# pc_sensything_v1_3.net
KiCad netlist of a schematic drawn in EAGLE
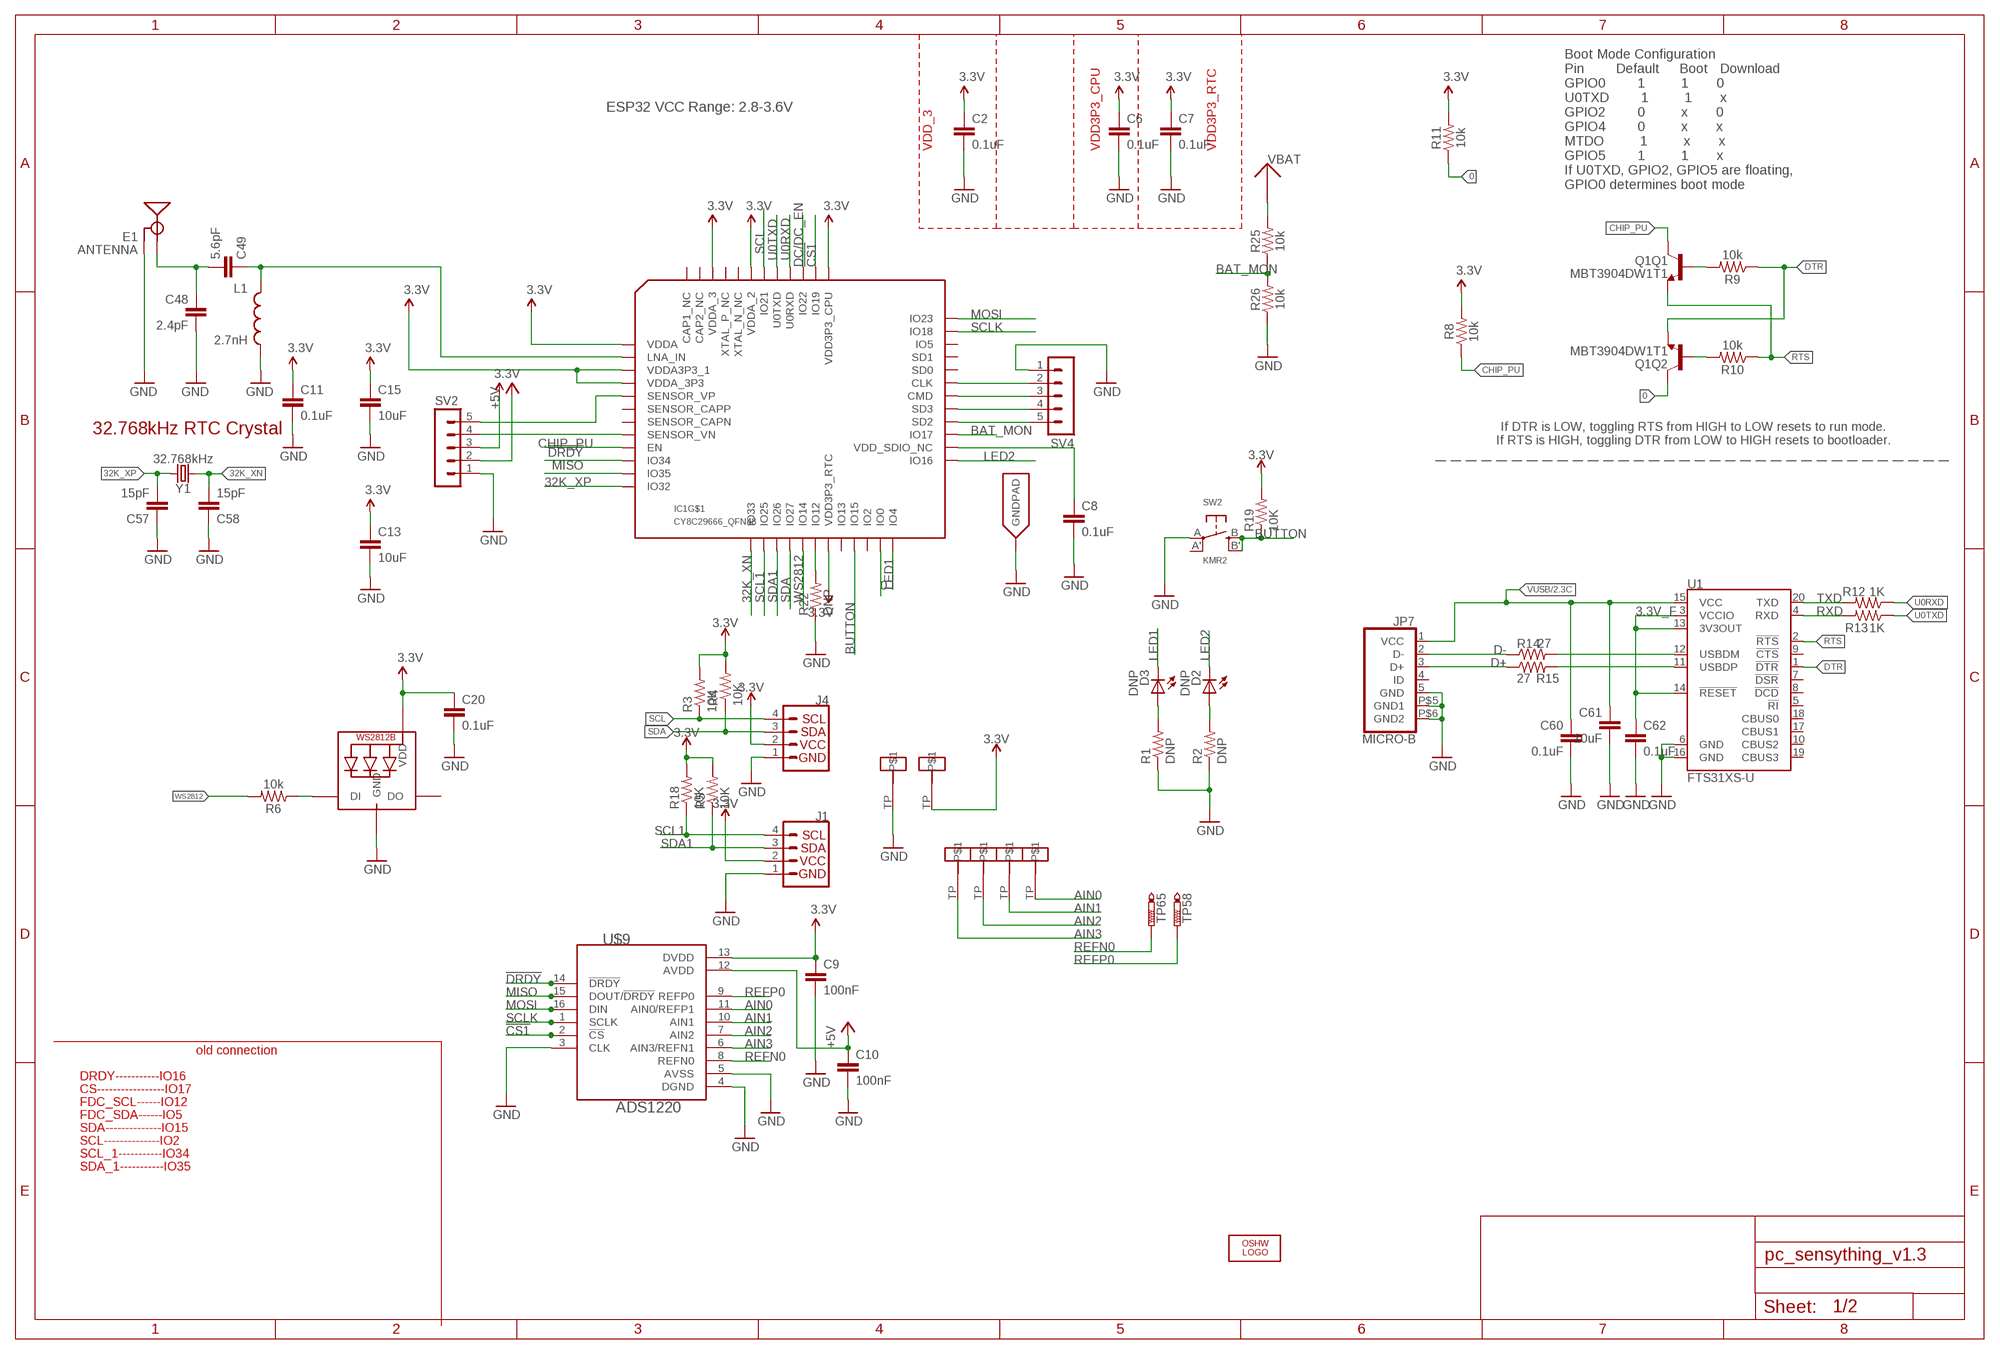
[diagram p0: schematic, sheet 1]
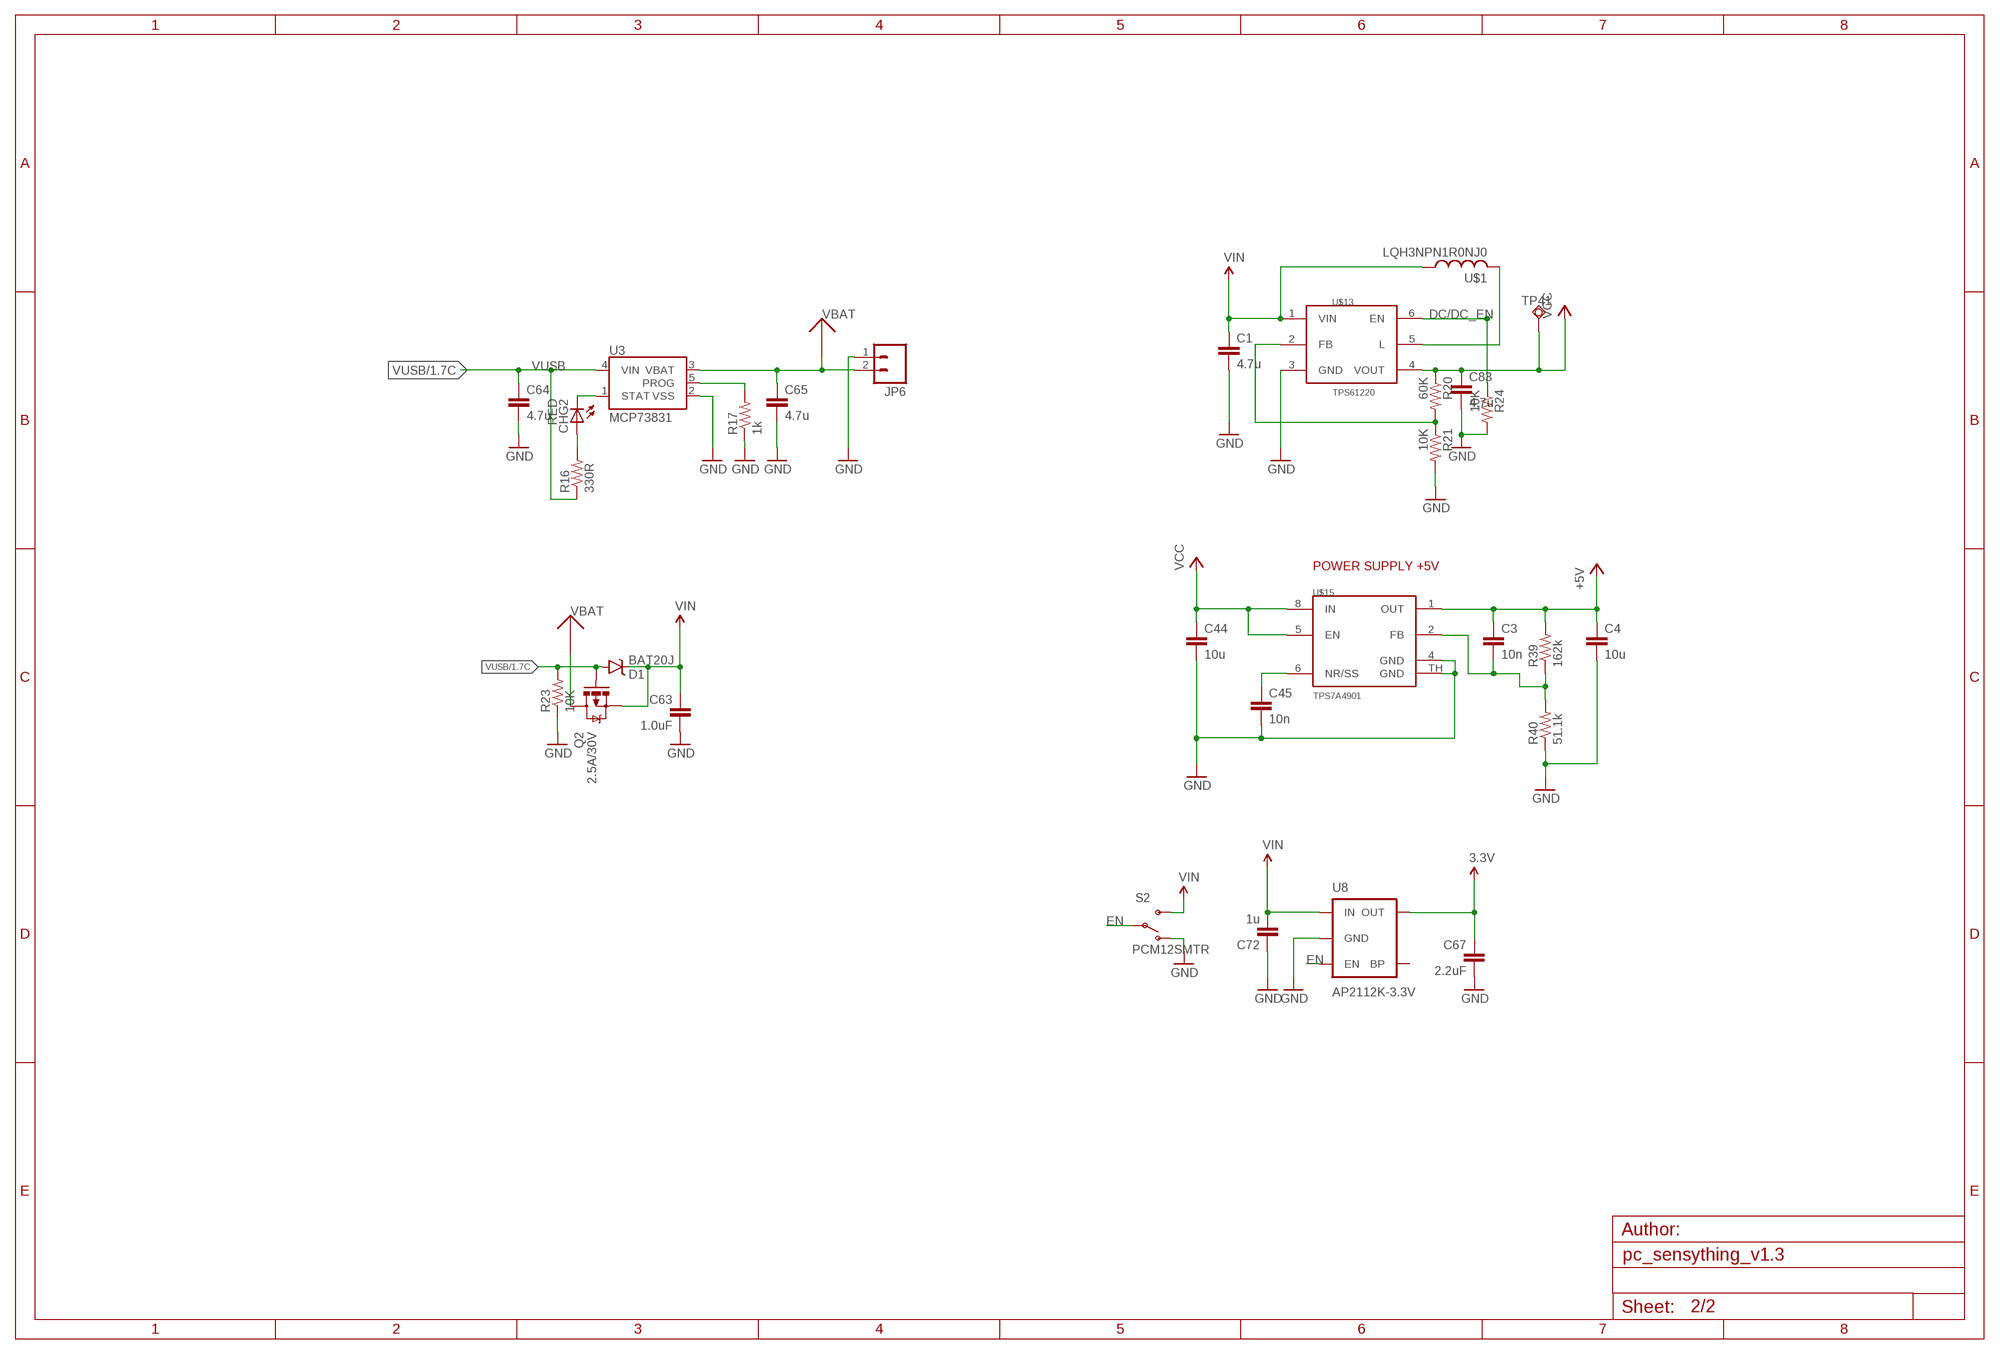
[diagram p1: schematic, sheet 2]

(export (version "E")
  (design (tool "Eeschema 10.0.6"))
  (components
    (comp (ref "C2")
      (value "0.1uF")
      (footprint "eagle-import:0402")
      (libsource (lib "eagle-import") (part "0.1UF-0402-16V-10%"))
    )
    (comp (ref "C6")
      (value "0.1uF")
      (footprint "eagle-import:0402")
      (libsource (lib "eagle-import") (part "0.1UF-0402-16V-10%"))
    )
    (comp (ref "C7")
      (value "0.1uF")
      (footprint "eagle-import:0402")
      (libsource (lib "eagle-import") (part "0.1UF-0402-16V-10%"))
    )
    (comp (ref "C8")
      (value "0.1uF")
      (footprint "eagle-import:0402")
      (libsource (lib "eagle-import") (part "0.1UF-0402-16V-10%"))
    )
    (comp (ref "C9")
      (value "100nF")
      (footprint "eagle-import:C0805")
      (libsource (lib "eagle-import") (part "C-EUC0805"))
    )
    (comp (ref "C10")
      (value "100nF")
      (footprint "eagle-import:C0805")
      (libsource (lib "eagle-import") (part "C-EUC0805"))
    )
    (comp (ref "C11")
      (value "0.1uF")
      (footprint "eagle-import:0402")
      (libsource (lib "eagle-import") (part "0.1UF-0402-16V-10%"))
    )
    (comp (ref "C13")
      (value "10uF")
      (footprint "eagle-import:0603")
      (libsource (lib "eagle-import") (part "10UF-0603-6.3V-20%"))
    )
    (comp (ref "C15")
      (value "10uF")
      (footprint "eagle-import:0603")
      (libsource (lib "eagle-import") (part "10UF-0603-6.3V-20%"))
    )
    (comp (ref "C20")
      (value "0.1uF")
      (footprint "eagle-import:0603")
      (libsource (lib "eagle-import") (part "0.1UF-0603-25V-(+80/-20%)"))
    )
    (comp (ref "C48")
      (value "2.4pF")
      (footprint "eagle-import:0603")
      (libsource (lib "eagle-import") (part "2.4PF-0603-50V-5%"))
    )
    (comp (ref "C49")
      (value "5.6pF")
      (footprint "eagle-import:0603")
      (libsource (lib "eagle-import") (part "5.6PF-50V-5%(0603)"))
    )
    (comp (ref "C57")
      (value "15pF")
      (footprint "eagle-import:0603")
      (libsource (lib "eagle-import") (part "15PF-0603-50V-5%"))
    )
    (comp (ref "C58")
      (value "15pF")
      (footprint "eagle-import:0603")
      (libsource (lib "eagle-import") (part "15PF-0603-50V-5%"))
    )
    (comp (ref "C60")
      (value "0.1uF")
      (footprint "eagle-import:C0402")
      (libsource (lib "eagle-import") (part "C-EUC0402"))
    )
    (comp (ref "C61")
      (value "10uF")
      (footprint "eagle-import:C0805")
      (libsource (lib "eagle-import") (part "C-EUC0805"))
    )
    (comp (ref "C62")
      (value "0.1uF")
      (footprint "eagle-import:C0402")
      (libsource (lib "eagle-import") (part "C-EUC0402"))
    )
    (comp (ref "D2")
      (value "DNP")
      (footprint "eagle-import:CHIPLED_0603")
      (libsource (lib "eagle-import") (part "LEDCHIPLED_0603"))
    )
    (comp (ref "D3")
      (value "DNP")
      (footprint "eagle-import:CHIPLED_0603")
      (libsource (lib "eagle-import") (part "LEDCHIPLED_0603"))
    )
    (comp (ref "E1")
      (value "ANTENNA")
      (footprint "eagle-import:TRACE_ANTENNA_2.4GHZ_25.7MM_TUNED")
      (libsource (lib "eagle-import") (part "ANTENNATRACE-TUNED"))
    )
    (comp (ref "IC1")
      (value "CY8C29666_QFN48")
      (footprint "eagle-import:QFN48")
      (libsource (lib "eagle-import") (part "CY8C29666_QFN48"))
    )
    (comp (ref "J1")
      (value "QWIIC_CONNECTORJS-1MM")
      (footprint "eagle-import:1X04_1MM_RA")
      (libsource (lib "eagle-import") (part "QWIIC_CONNECTORJS-1MM"))
    )
    (comp (ref "J4")
      (value "QWIIC_CONNECTORJS-1MM")
      (footprint "eagle-import:1X04_1MM_RA")
      (libsource (lib "eagle-import") (part "QWIIC_CONNECTORJS-1MM"))
    )
    (comp (ref "JP7")
      (value "MICRO-B")
      (footprint "eagle-import:MICRO-B")
      (libsource (lib "eagle-import") (part "MICRO-B"))
    )
    (comp (ref "L1")
      (value "2.7nH")
      (footprint "eagle-import:0603")
      (libsource (lib "eagle-import") (part "INDUCTOR0603"))
    )
    (comp (ref "LED1")
      (value "WS2812B5050")
      (footprint "eagle-import:WS2812B")
      (libsource (lib "eagle-import") (part "WS2812B5050"))
    )
    (comp (ref "LOGO3")
      (value "OSHW_LOGO_FILLX0200-NT")
      (footprint "eagle-import:OSHW_FILLX200_NOTEXT")
      (libsource (lib "eagle-import") (part "OSHW_LOGO_FILLX0200-NT"))
    )
    (comp (ref "Q1")
      (value "MBT3904DW1T1")
      (footprint "eagle-import:SC70-6")
      (libsource (lib "eagle-import") (part "MBT3904DW1T1"))
    )
    (comp (ref "R1")
      (value "DNP")
      (footprint "eagle-import:R0402")
      (libsource (lib "eagle-import") (part "R-US_R0402"))
    )
    (comp (ref "R2")
      (value "DNP")
      (footprint "eagle-import:R0402")
      (libsource (lib "eagle-import") (part "R-US_R0402"))
    )
    (comp (ref "R3")
      (value "10K")
      (footprint "eagle-import:R0402")
      (libsource (lib "eagle-import") (part "R-US_R0402"))
    )
    (comp (ref "R4")
      (value "10K")
      (footprint "eagle-import:R0402")
      (libsource (lib "eagle-import") (part "R-US_R0402"))
    )
    (comp (ref "R5")
      (value "10K")
      (footprint "eagle-import:R0402")
      (libsource (lib "eagle-import") (part "R-US_R0402"))
    )
    (comp (ref "R6")
      (value "10k")
      (footprint "eagle-import:0603")
      (libsource (lib "eagle-import") (part "10KOHM-1/10W-1%(0603)0603"))
    )
    (comp (ref "R8")
      (value "10k")
      (footprint "eagle-import:0603")
      (libsource (lib "eagle-import") (part "10KOHM-1/10W-1%(0603)0603"))
    )
    (comp (ref "R9")
      (value "10k")
      (footprint "eagle-import:0603")
      (libsource (lib "eagle-import") (part "10KOHM-0603-1/10W-1%"))
    )
    (comp (ref "R10")
      (value "10k")
      (footprint "eagle-import:0603")
      (libsource (lib "eagle-import") (part "10KOHM-0603-1/10W-1%"))
    )
    (comp (ref "R11")
      (value "10k")
      (footprint "eagle-import:0603")
      (libsource (lib "eagle-import") (part "10KOHM-1/10W-1%(0603)0603"))
    )
    (comp (ref "R12")
      (value "1K")
      (footprint "eagle-import:R0402")
      (libsource (lib "eagle-import") (part "R-US_R0402"))
    )
    (comp (ref "R13")
      (value "1K")
      (footprint "eagle-import:R0402")
      (libsource (lib "eagle-import") (part "R-US_R0402"))
    )
    (comp (ref "R14")
      (value "27")
      (footprint "eagle-import:R0402")
      (libsource (lib "eagle-import") (part "R-US_R0402"))
    )
    (comp (ref "R15")
      (value "27")
      (footprint "eagle-import:R0402")
      (libsource (lib "eagle-import") (part "R-US_R0402"))
    )
    (comp (ref "R18")
      (value "10K")
      (footprint "eagle-import:R0402")
      (libsource (lib "eagle-import") (part "R-US_R0402"))
    )
    (comp (ref "R19")
      (value "10K")
      (footprint "eagle-import:R0402")
      (libsource (lib "eagle-import") (part "R-US_R0402"))
    )
    (comp (ref "R22")
      (value "DNP")
      (footprint "eagle-import:R0402")
      (libsource (lib "eagle-import") (part "R-US_R0402"))
    )
    (comp (ref "R25")
      (value "10k")
      (footprint "eagle-import:0603")
      (libsource (lib "eagle-import") (part "10KOHM-1/10W-1%(0603)0603"))
    )
    (comp (ref "R26")
      (value "10k")
      (footprint "eagle-import:0603")
      (libsource (lib "eagle-import") (part "10KOHM-1/10W-1%(0603)0603"))
    )
    (comp (ref "SV2")
      (value "MA05-1")
      (footprint "eagle-import:MA05-1")
      (libsource (lib "eagle-import") (part "MA05-1"))
    )
    (comp (ref "SV4")
      (value "MA05-1")
      (footprint "eagle-import:MA05-1")
      (libsource (lib "eagle-import") (part "MA05-1"))
    )
    (comp (ref "SW2")
      (value "KMR2")
      (footprint "eagle-import:BTN_KMR2_4.6X2.8")
      (libsource (lib "eagle-import") (part "SWITCH_TACT_SMT4.6X2.8"))
    )
    (comp (ref "TP58")
      (value "PTR1PAD1-13")
      (footprint "eagle-import:P1-13")
      (libsource (lib "eagle-import") (part "PTR1PAD1-13"))
    )
    (comp (ref "TP65")
      (value "PTR1PAD1-13")
      (footprint "eagle-import:P1-13")
      (libsource (lib "eagle-import") (part "PTR1PAD1-13"))
    )
    (comp (ref "U$3")
      (value "SENSYTHING_CON")
      (footprint "eagle-import:SENSYTHING_CON")
      (libsource (lib "eagle-import") (part "SENSYTHING_CON"))
    )
    (comp (ref "U$7")
      (value "SENSYTHING_CON")
      (footprint "eagle-import:SENSYTHING_CON")
      (libsource (lib "eagle-import") (part "SENSYTHING_CON"))
    )
    (comp (ref "U$8")
      (value "SENSYTHING_CON")
      (footprint "eagle-import:SENSYTHING_CON")
      (libsource (lib "eagle-import") (part "SENSYTHING_CON"))
    )
    (comp (ref "U$9")
      (value "ADS1220")
      (footprint "eagle-import:TSSOP-16")
      (libsource (lib "eagle-import") (part "ADS1220"))
    )
    (comp (ref "U$11")
      (value "SENSYTHING_CON")
      (footprint "eagle-import:SENSYTHING_CON")
      (libsource (lib "eagle-import") (part "SENSYTHING_CON"))
    )
    (comp (ref "U$12")
      (value "SENSYTHING_CON")
      (footprint "eagle-import:SENSYTHING_CON")
      (libsource (lib "eagle-import") (part "SENSYTHING_CON"))
    )
    (comp (ref "U$14")
      (value "SENSYTHING_CON")
      (footprint "eagle-import:SENSYTHING_CON")
      (libsource (lib "eagle-import") (part "SENSYTHING_CON"))
    )
    (comp (ref "U1")
      (value "FTS31XS-U")
      (footprint "eagle-import:SSOP20_L")
      (libsource (lib "eagle-import") (part "FT231XS"))
    )
    (comp (ref "Y1")
      (value "32.768kHz")
      (footprint "eagle-import:CRYSTAL-SMD-3.2X1.5MM")
      (libsource (lib "eagle-import") (part "CRYSTAL-32.768KHZSMD-3.2X1.5"))
    )
    (comp (ref "C1")
      (value "4.7u")
      (footprint "eagle-import:C0805")
      (libsource (lib "eagle-import") (part "C-EUC0805"))
    )
    (comp (ref "C3")
      (value "10n")
      (footprint "eagle-import:C0402")
      (libsource (lib "eagle-import") (part "C-EUC0402"))
    )
    (comp (ref "C4")
      (value "10u")
      (footprint "eagle-import:C0805")
      (libsource (lib "eagle-import") (part "C-EUC0805"))
    )
    (comp (ref "C44")
      (value "10u")
      (footprint "eagle-import:C0805")
      (libsource (lib "eagle-import") (part "C-EUC0805"))
    )
    (comp (ref "C45")
      (value "10n")
      (footprint "eagle-import:C0402")
      (libsource (lib "eagle-import") (part "C-EUC0402"))
    )
    (comp (ref "C63")
      (value "1.0uF")
      (footprint "eagle-import:C0402")
      (libsource (lib "eagle-import") (part "C-EUC0402"))
    )
    (comp (ref "C64")
      (value "4.7u")
      (footprint "eagle-import:C0805")
      (libsource (lib "eagle-import") (part "C-EUC0805"))
    )
    (comp (ref "C65")
      (value "4.7u")
      (footprint "eagle-import:C0805")
      (libsource (lib "eagle-import") (part "C-EUC0805"))
    )
    (comp (ref "C67")
      (value "2.2uF")
      (footprint "eagle-import:C0402")
      (libsource (lib "eagle-import") (part "C-EUC0402"))
    )
    (comp (ref "C72")
      (value "1u")
      (footprint "eagle-import:C0402")
      (libsource (lib "eagle-import") (part "C-EUC0402"))
    )
    (comp (ref "C83")
      (value "4.7u")
      (footprint "eagle-import:C0805")
      (libsource (lib "eagle-import") (part "C-EUC0805"))
    )
    (comp (ref "CHG2")
      (value "RED")
      (footprint "eagle-import:CHIPLED_0603")
      (libsource (lib "eagle-import") (part "LEDCHIPLED_0603"))
    )
    (comp (ref "D1")
      (value "BAT20J")
      (footprint "eagle-import:SOD-323")
      (libsource (lib "eagle-import") (part "DIODE-SCHOTTKY-BAT20J"))
    )
    (comp (ref "JP6")
      (value "M02-JST-2MM-SMT")
      (footprint "eagle-import:JST-2-SMD")
      (libsource (lib "eagle-import") (part "M02-JST-2MM-SMT"))
    )
    (comp (ref "Q2")
      (value "2.5A/30V")
      (footprint "eagle-import:SOT23-3")
      (libsource (lib "eagle-import") (part "MOSFET-PCHANNELDMG2307L"))
    )
    (comp (ref "R16")
      (value "330R")
      (footprint "eagle-import:R0402")
      (libsource (lib "eagle-import") (part "R-US_R0402"))
    )
    (comp (ref "R17")
      (value "1k")
      (footprint "eagle-import:R0402")
      (libsource (lib "eagle-import") (part "R-US_R0402"))
    )
    (comp (ref "R20")
      (value "60K")
      (footprint "eagle-import:R0805")
      (libsource (lib "eagle-import") (part "R-US_R0805"))
    )
    (comp (ref "R21")
      (value "10K")
      (footprint "eagle-import:R0805")
      (libsource (lib "eagle-import") (part "R-US_R0805"))
    )
    (comp (ref "R23")
      (value "10K")
      (footprint "eagle-import:R0402")
      (libsource (lib "eagle-import") (part "R-US_R0402"))
    )
    (comp (ref "R24")
      (value "10K")
      (footprint "eagle-import:R0402")
      (libsource (lib "eagle-import") (part "R-US_R0402"))
    )
    (comp (ref "R39")
      (value "162k")
      (footprint "eagle-import:R0805")
      (libsource (lib "eagle-import") (part "R-US_R0805"))
    )
    (comp (ref "R40")
      (value "51.1k")
      (footprint "eagle-import:R0805")
      (libsource (lib "eagle-import") (part "R-US_R0805"))
    )
    (comp (ref "S2")
      (value "PCM12SMTR")
      (footprint "eagle-import:SWITCH-SPST-SMD-A")
      (libsource (lib "eagle-import") (part "SWITCH-SPDT-SMD-A"))
    )
    (comp (ref "TP41")
      (value "TPSQB1,27")
      (footprint "eagle-import:B1,27")
      (libsource (lib "eagle-import") (part "TPSQB1,27"))
    )
    (comp (ref "U$1")
      (value "LQH3NPN1R0NJ0")
      (footprint "eagle-import:LQH3NP")
      (libsource (lib "eagle-import") (part "LQH3NPN1R0NJ0"))
    )
    (comp (ref "U$13")
      (value "TPS61220")
      (footprint "eagle-import:SC-70-6")
      (libsource (lib "eagle-import") (part "TPS61222"))
    )
    (comp (ref "U$15")
      (value "TPS7A4901")
      (footprint "eagle-import:S-PDSO-G08")
      (libsource (lib "eagle-import") (part "TPS7A4901"))
    )
    (comp (ref "U3")
      (value "MCP73831")
      (footprint "eagle-import:SOT23-5")
      (libsource (lib "eagle-import") (part "MCP73831"))
    )
    (comp (ref "U8")
      (value "AP2112K-3.3V")
      (footprint "eagle-import:SOT23-5")
      (libsource (lib "eagle-import") (part "V_REG_LDOSMD"))
    )
  )
  (nets
    (net (code "1") (name "+5V") (class "Default")
      (node (ref "C10") (pin "1") (pinfunction "1_1") (pintype "passive"))
      (node (ref "C3") (pin "1") (pinfunction "1_1") (pintype "passive"))
      (node (ref "C4") (pin "1") (pinfunction "1_1") (pintype "passive"))
      (node (ref "R39") (pin "2") (pinfunction "2_2") (pintype "passive"))
      (node (ref "SV2") (pin "2") (pinfunction "2_2") (pintype "passive"))
      (node (ref "U$15") (pin "1") (pinfunction "OUT_1") (pintype "bidirectional"))
      (node (ref "U$9") (pin "12") (pinfunction "AVDD_12") (pintype "bidirectional"))
    )
    (net (code "2") (name "0") (class "Default")
      (node (ref "IC1") (pin "23") (pinfunction "IO0_23") (pintype "bidirectional"))
      (node (ref "Q1") (pin "6") (pinfunction "C_6") (pintype "passive"))
      (node (ref "R11") (pin "1") (pinfunction "1_1") (pintype "passive"))
    )
    (net (code "3") (name "3.3V") (class "Default")
      (node (ref "C11") (pin "1") (pinfunction "1_1") (pintype "passive"))
      (node (ref "C13") (pin "1") (pinfunction "1_1") (pintype "passive"))
      (node (ref "C15") (pin "1") (pinfunction "1_1") (pintype "passive"))
      (node (ref "C2") (pin "1") (pinfunction "1_1") (pintype "passive"))
      (node (ref "C20") (pin "1") (pinfunction "1_1") (pintype "passive"))
      (node (ref "C6") (pin "1") (pinfunction "1_1") (pintype "passive"))
      (node (ref "C67") (pin "1") (pinfunction "1_1") (pintype "passive"))
      (node (ref "C7") (pin "1") (pinfunction "1_1") (pintype "passive"))
      (node (ref "C9") (pin "1") (pinfunction "1_1") (pintype "passive"))
      (node (ref "IC1") (pin "1") (pinfunction "VDDA_1") (pintype "bidirectional"))
      (node (ref "IC1") (pin "19") (pinfunction "VDD3P3_RTC_19") (pintype "bidirectional"))
      (node (ref "IC1") (pin "3") (pinfunction "VDDA3P3_1_3") (pintype "bidirectional"))
      (node (ref "IC1") (pin "37") (pinfunction "VDD3P3_CPU_37") (pintype "bidirectional"))
      (node (ref "IC1") (pin "4") (pinfunction "VDDA_3P3_4") (pintype "bidirectional"))
      (node (ref "IC1") (pin "43") (pinfunction "VDDA_2_43") (pintype "bidirectional"))
      (node (ref "IC1") (pin "46") (pinfunction "VDDA_3_46") (pintype "bidirectional"))
      (node (ref "J1") (pin "2") (pinfunction "2_2") (pintype "power_in"))
      (node (ref "J4") (pin "2") (pinfunction "2_2") (pintype "power_in"))
      (node (ref "LED1") (pin "1-VDD") (pinfunction "VDD_1-VDD") (pintype "power_in"))
      (node (ref "R11") (pin "2") (pinfunction "2_2") (pintype "passive"))
      (node (ref "R18") (pin "2") (pinfunction "2_2") (pintype "passive"))
      (node (ref "R19") (pin "2") (pinfunction "2_2") (pintype "passive"))
      (node (ref "R3") (pin "2") (pinfunction "2_2") (pintype "passive"))
      (node (ref "R4") (pin "2") (pinfunction "2_2") (pintype "passive"))
      (node (ref "R5") (pin "2") (pinfunction "2_2") (pintype "passive"))
      (node (ref "R8") (pin "2") (pinfunction "2_2") (pintype "passive"))
      (node (ref "SV2") (pin "3") (pinfunction "3_3") (pintype "passive"))
      (node (ref "U$14") (pin "TP") (pinfunction "P$1_TP") (pintype "bidirectional"))
      (node (ref "U$9") (pin "13") (pinfunction "DVDD_13") (pintype "bidirectional"))
      (node (ref "U8") (pin "5") (pinfunction "OUT_5") (pintype "passive"))
    )
    (net (code "4") (name "3.3V_F") (class "Default")
      (node (ref "C62") (pin "1") (pinfunction "1_1") (pintype "passive"))
      (node (ref "U1") (pin "13") (pinfunction "3V3OUT_13") (pintype "bidirectional"))
      (node (ref "U1") (pin "14") (pinfunction "~{RESET}_14") (pintype "bidirectional"))
      (node (ref "U1") (pin "3") (pinfunction "VCCIO_3") (pintype "bidirectional"))
    )
    (net (code "5") (name "32K_XN") (class "Default")
      (node (ref "C58") (pin "2") (pinfunction "2_2") (pintype "passive"))
      (node (ref "IC1") (pin "13") (pinfunction "IO33_13") (pintype "bidirectional"))
      (node (ref "Y1") (pin "P$2") (pinfunction "2_P$2") (pintype "passive"))
    )
    (net (code "6") (name "32K_XP") (class "Default")
      (node (ref "C57") (pin "2") (pinfunction "2_2") (pintype "passive"))
      (node (ref "IC1") (pin "12") (pinfunction "IO32_12") (pintype "bidirectional"))
      (node (ref "Y1") (pin "P$1") (pinfunction "1_P$1") (pintype "passive"))
    )
    (net (code "7") (name "AIN0") (class "Default")
      (node (ref "U$11") (pin "TP") (pinfunction "P$1_TP") (pintype "bidirectional"))
      (node (ref "U$9") (pin "11") (pinfunction "AIN0/REFP1_11") (pintype "bidirectional"))
    )
    (net (code "8") (name "AIN1") (class "Default")
      (node (ref "U$8") (pin "TP") (pinfunction "P$1_TP") (pintype "bidirectional"))
      (node (ref "U$9") (pin "10") (pinfunction "AIN1_10") (pintype "bidirectional"))
    )
    (net (code "9") (name "AIN2") (class "Default")
      (node (ref "U$7") (pin "TP") (pinfunction "P$1_TP") (pintype "bidirectional"))
      (node (ref "U$9") (pin "7") (pinfunction "AIN2_7") (pintype "bidirectional"))
    )
    (net (code "10") (name "AIN3") (class "Default")
      (node (ref "U$3") (pin "TP") (pinfunction "P$1_TP") (pintype "bidirectional"))
      (node (ref "U$9") (pin "6") (pinfunction "AIN3/REFN1_6") (pintype "bidirectional"))
    )
    (net (code "11") (name "BAT_MON") (class "Default")
      (node (ref "IC1") (pin "27") (pinfunction "IO17_27") (pintype "bidirectional"))
      (node (ref "R25") (pin "1") (pinfunction "1_1") (pintype "passive"))
      (node (ref "R26") (pin "2") (pinfunction "2_2") (pintype "passive"))
    )
    (net (code "12") (name "BUTTON") (class "Default")
      (node (ref "IC1") (pin "21") (pinfunction "IO15_21") (pintype "bidirectional"))
      (node (ref "R19") (pin "1") (pinfunction "1_1") (pintype "passive"))
      (node (ref "SW2") (pin "B") (pinfunction "S_B") (pintype "passive"))
      (node (ref "SW2") (pin "B'") (pinfunction "S1_B'") (pintype "passive"))
    )
    (net (code "13") (name "CHIP_PU") (class "Default")
      (node (ref "IC1") (pin "9") (pinfunction "EN_9") (pintype "bidirectional"))
      (node (ref "Q1") (pin "3") (pinfunction "C_3") (pintype "passive"))
      (node (ref "R8") (pin "1") (pinfunction "1_1") (pintype "passive"))
    )
    (net (code "14") (name "D+") (class "Default")
      (node (ref "JP7") (pin "3") (pinfunction "D+_3") (pintype "bidirectional"))
      (node (ref "R15") (pin "1") (pinfunction "1_1") (pintype "passive"))
    )
    (net (code "15") (name "D-") (class "Default")
      (node (ref "JP7") (pin "2") (pinfunction "D-_2") (pintype "bidirectional"))
      (node (ref "R14") (pin "1") (pinfunction "1_1") (pintype "passive"))
    )
    (net (code "16") (name "DC{slash}DC_EN") (class "Default")
      (node (ref "IC1") (pin "39") (pinfunction "IO22_39") (pintype "bidirectional"))
      (node (ref "R24") (pin "1") (pinfunction "1_1") (pintype "passive"))
      (node (ref "U$13") (pin "6") (pinfunction "EN_6") (pintype "bidirectional"))
    )
    (net (code "17") (name "DTR") (class "Default")
      (node (ref "Q1") (pin "1") (pinfunction "E_1") (pintype "passive"))
      (node (ref "R9") (pin "1") (pinfunction "1_1") (pintype "passive"))
      (node (ref "U1") (pin "1") (pinfunction "~{DTR}_1") (pintype "bidirectional"))
    )
    (net (code "18") (name "EN") (class "Default")
      (node (ref "S2") (pin "2") (pinfunction "P_2") (pintype "passive"))
      (node (ref "U8") (pin "3") (pinfunction "EN_3") (pintype "input"))
    )
    (net (code "19") (name "GND") (class "Default")
      (node (ref "C1") (pin "2") (pinfunction "2_2") (pintype "passive"))
      (node (ref "C10") (pin "2") (pinfunction "2_2") (pintype "passive"))
      (node (ref "C11") (pin "2") (pinfunction "2_2") (pintype "passive"))
      (node (ref "C13") (pin "2") (pinfunction "2_2") (pintype "passive"))
      (node (ref "C15") (pin "2") (pinfunction "2_2") (pintype "passive"))
      (node (ref "C2") (pin "2") (pinfunction "2_2") (pintype "passive"))
      (node (ref "C20") (pin "2") (pinfunction "2_2") (pintype "passive"))
      (node (ref "C4") (pin "2") (pinfunction "2_2") (pintype "passive"))
      (node (ref "C44") (pin "2") (pinfunction "2_2") (pintype "passive"))
      (node (ref "C45") (pin "2") (pinfunction "2_2") (pintype "passive"))
      (node (ref "C48") (pin "2") (pinfunction "2_2") (pintype "passive"))
      (node (ref "C57") (pin "1") (pinfunction "1_1") (pintype "passive"))
      (node (ref "C58") (pin "1") (pinfunction "1_1") (pintype "passive"))
      (node (ref "C6") (pin "2") (pinfunction "2_2") (pintype "passive"))
      (node (ref "C60") (pin "2") (pinfunction "2_2") (pintype "passive"))
      (node (ref "C61") (pin "2") (pinfunction "2_2") (pintype "passive"))
      (node (ref "C62") (pin "2") (pinfunction "2_2") (pintype "passive"))
      (node (ref "C63") (pin "2") (pinfunction "2_2") (pintype "passive"))
      (node (ref "C64") (pin "2") (pinfunction "2_2") (pintype "passive"))
      (node (ref "C65") (pin "2") (pinfunction "2_2") (pintype "passive"))
      (node (ref "C67") (pin "2") (pinfunction "2_2") (pintype "passive"))
      (node (ref "C7") (pin "2") (pinfunction "2_2") (pintype "passive"))
      (node (ref "C72") (pin "1") (pinfunction "1_1") (pintype "passive"))
      (node (ref "C8") (pin "2") (pinfunction "2_2") (pintype "passive"))
      (node (ref "C83") (pin "2") (pinfunction "2_2") (pintype "passive"))
      (node (ref "C9") (pin "2") (pinfunction "2_2") (pintype "passive"))
      (node (ref "E1") (pin "GND") (pinfunction "GND_GND") (pintype "bidirectional"))
      (node (ref "E1") (pin "GND2") (pinfunction "GND_GND2") (pintype "bidirectional"))
      (node (ref "IC1") (pin "EXP") (pinfunction "GNDPAD_EXP") (pintype "power_in"))
      (node (ref "J1") (pin "1") (pinfunction "1_1") (pintype "power_in"))
      (node (ref "J4") (pin "1") (pinfunction "1_1") (pintype "power_in"))
      (node (ref "JP6") (pin "1") (pinfunction "1_1") (pintype "passive"))
      (node (ref "JP7") (pin "5") (pinfunction "GND_5") (pintype "bidirectional"))
      (node (ref "JP7") (pin "P$5") (pinfunction "GND1_P$5") (pintype "bidirectional"))
      (node (ref "JP7") (pin "P$6") (pinfunction "GND2_P$6") (pintype "bidirectional"))
      (node (ref "L1") (pin "2") (pinfunction "2_2") (pintype "passive"))
      (node (ref "LED1") (pin "3-GND") (pinfunction "GND_3-GND") (pintype "power_in"))
      (node (ref "R1") (pin "1") (pinfunction "1_1") (pintype "passive"))
      (node (ref "R17") (pin "1") (pinfunction "1_1") (pintype "passive"))
      (node (ref "R2") (pin "1") (pinfunction "1_1") (pintype "passive"))
      (node (ref "R21") (pin "2") (pinfunction "2_2") (pintype "passive"))
      (node (ref "R22") (pin "1") (pinfunction "1_1") (pintype "passive"))
      (node (ref "R23") (pin "1") (pinfunction "1_1") (pintype "passive"))
      (node (ref "R24") (pin "2") (pinfunction "2_2") (pintype "passive"))
      (node (ref "R26") (pin "1") (pinfunction "1_1") (pintype "passive"))
      (node (ref "R40") (pin "1") (pinfunction "1_1") (pintype "passive"))
      (node (ref "S2") (pin "1") (pinfunction "O_1") (pintype "passive"))
      (node (ref "SV2") (pin "1") (pinfunction "1_1") (pintype "passive"))
      (node (ref "SV4") (pin "1") (pinfunction "1_1") (pintype "passive"))
      (node (ref "SW2") (pin "A") (pinfunction "P_A") (pintype "passive"))
      (node (ref "U$12") (pin "TP") (pinfunction "P$1_TP") (pintype "bidirectional"))
      (node (ref "U$13") (pin "3") (pinfunction "GND_3") (pintype "bidirectional"))
      (node (ref "U$15") (pin "4") (pinfunction "GND_4") (pintype "bidirectional"))
      (node (ref "U$15") (pin "TH") (pinfunction "GND_TH") (pintype "bidirectional"))
      (node (ref "U$9") (pin "3") (pinfunction "CLK_3") (pintype "bidirectional"))
      (node (ref "U$9") (pin "4") (pinfunction "DGND_4") (pintype "bidirectional"))
      (node (ref "U$9") (pin "5") (pinfunction "AVSS_5") (pintype "bidirectional"))
      (node (ref "U1") (pin "16") (pinfunction "GND_16") (pintype "bidirectional"))
      (node (ref "U1") (pin "6") (pinfunction "GND_6") (pintype "bidirectional"))
      (node (ref "U3") (pin "2") (pinfunction "VSS_2") (pintype "power_in"))
      (node (ref "U8") (pin "2") (pinfunction "GND_2") (pintype "input"))
    )
    (net (code "20") (name "LED1") (class "Default")
      (node (ref "D3") (pin "C") (pinfunction "C_C") (pintype "passive"))
      (node (ref "IC1") (pin "24") (pinfunction "IO4_24") (pintype "bidirectional"))
    )
    (net (code "21") (name "LED2") (class "Default")
      (node (ref "D2") (pin "C") (pinfunction "C_C") (pintype "passive"))
      (node (ref "IC1") (pin "25") (pinfunction "IO16_25") (pintype "bidirectional"))
    )
    (net (code "22") (name "MISO") (class "Default")
      (node (ref "IC1") (pin "11") (pinfunction "IO35_11") (pintype "bidirectional"))
      (node (ref "U$9") (pin "15") (pinfunction "DOUT/~{DRDY}_15") (pintype "bidirectional"))
    )
    (net (code "23") (name "MOSI") (class "Default")
      (node (ref "IC1") (pin "36") (pinfunction "IO23_36") (pintype "bidirectional"))
      (node (ref "U$9") (pin "16") (pinfunction "DIN_16") (pintype "bidirectional"))
    )
    (net (code "24") (name "Net-(CHG2-PadA)") (class "Default")
      (node (ref "CHG2") (pin "A") (pinfunction "A_A") (pintype "passive"))
      (node (ref "R16") (pin "2") (pinfunction "2_2") (pintype "passive"))
    )
    (net (code "25") (name "Net-(D2-PadA)") (class "Default")
      (node (ref "D2") (pin "A") (pinfunction "A_A") (pintype "passive"))
      (node (ref "R2") (pin "2") (pinfunction "2_2") (pintype "passive"))
    )
    (net (code "26") (name "Net-(D3-PadA)") (class "Default")
      (node (ref "D3") (pin "A") (pinfunction "A_A") (pintype "passive"))
      (node (ref "R1") (pin "2") (pinfunction "2_2") (pintype "passive"))
    )
    (net (code "27") (name "Net-(E1-SIGNAL)") (class "Default")
      (node (ref "C48") (pin "1") (pinfunction "1_1") (pintype "passive"))
      (node (ref "C49") (pin "2") (pinfunction "2_2") (pintype "passive"))
      (node (ref "E1") (pin "ANT") (pinfunction "SIGNAL_ANT") (pintype "bidirectional"))
    )
    (net (code "28") (name "Net-(IC1A-CLK)") (class "Default")
      (node (ref "IC1") (pin "31") (pinfunction "CLK_31") (pintype "bidirectional"))
      (node (ref "SV4") (pin "2") (pinfunction "2_2") (pintype "passive"))
    )
    (net (code "29") (name "Net-(IC1A-CMD)") (class "Default")
      (node (ref "IC1") (pin "30") (pinfunction "CMD_30") (pintype "bidirectional"))
      (node (ref "SV4") (pin "3") (pinfunction "3_3") (pintype "passive"))
    )
    (net (code "30") (name "Net-(IC1A-IO12)") (class "Default")
      (node (ref "IC1") (pin "18") (pinfunction "IO12_18") (pintype "power_in"))
      (node (ref "R22") (pin "2") (pinfunction "2_2") (pintype "passive"))
    )
    (net (code "31") (name "Net-(IC1A-LNA_IN)") (class "Default")
      (node (ref "C49") (pin "1") (pinfunction "1_1") (pintype "passive"))
      (node (ref "IC1") (pin "2") (pinfunction "LNA_IN_2") (pintype "bidirectional"))
      (node (ref "L1") (pin "1") (pinfunction "1_1") (pintype "passive"))
    )
    (net (code "32") (name "Net-(IC1A-SD2)") (class "Default")
      (node (ref "IC1") (pin "28") (pinfunction "SD2_28") (pintype "bidirectional"))
      (node (ref "SV4") (pin "5") (pinfunction "5_5") (pintype "passive"))
    )
    (net (code "33") (name "Net-(IC1A-SD3)") (class "Default")
      (node (ref "IC1") (pin "29") (pinfunction "SD3_29") (pintype "bidirectional"))
      (node (ref "SV4") (pin "4") (pinfunction "4_4") (pintype "passive"))
    )
    (net (code "34") (name "Net-(IC1A-SENSOR_VN)") (class "Default")
      (node (ref "IC1") (pin "8") (pinfunction "SENSOR_VN_8") (pintype "bidirectional"))
      (node (ref "SV2") (pin "4") (pinfunction "4_4") (pintype "passive"))
    )
    (net (code "35") (name "Net-(IC1A-SENSOR_VP)") (class "Default")
      (node (ref "IC1") (pin "5") (pinfunction "SENSOR_VP_5") (pintype "bidirectional"))
      (node (ref "SV2") (pin "5") (pinfunction "5_5") (pintype "passive"))
    )
    (net (code "36") (name "Net-(IC1A-VDD_SDIO_NC)") (class "Default")
      (node (ref "C8") (pin "1") (pinfunction "1_1") (pintype "passive"))
      (node (ref "IC1") (pin "26") (pinfunction "VDD_SDIO_NC_26") (pintype "bidirectional"))
    )
    (net (code "37") (name "Net-(LED1-DI)") (class "Default")
      (node (ref "LED1") (pin "4-DIN") (pinfunction "DI_4-DIN") (pintype "input"))
      (node (ref "R6") (pin "1") (pinfunction "1_1") (pintype "passive"))
    )
    (net (code "38") (name "Net-(Q1A-B)") (class "Default")
      (node (ref "Q1") (pin "5") (pinfunction "B_5") (pintype "passive"))
      (node (ref "R9") (pin "2") (pinfunction "2_2") (pintype "passive"))
    )
    (net (code "39") (name "Net-(Q1B-B)") (class "Default")
      (node (ref "Q1") (pin "2") (pinfunction "B_2") (pintype "passive"))
      (node (ref "R10") (pin "2") (pinfunction "2_2") (pintype "passive"))
    )
    (net (code "40") (name "Net-(U$1-2)") (class "Default")
      (node (ref "U$1") (pin "P$2") (pinfunction "2_P$2") (pintype "passive"))
      (node (ref "U$13") (pin "5") (pinfunction "L_5") (pintype "bidirectional"))
    )
    (net (code "41") (name "Net-(U$13-FB)") (class "Default")
      (node (ref "R20") (pin "2") (pinfunction "2_2") (pintype "passive"))
      (node (ref "R21") (pin "1") (pinfunction "1_1") (pintype "passive"))
      (node (ref "U$13") (pin "2") (pinfunction "FB_2") (pintype "bidirectional"))
    )
    (net (code "42") (name "Net-(U$15-FB)") (class "Default")
      (node (ref "C3") (pin "2") (pinfunction "2_2") (pintype "passive"))
      (node (ref "R39") (pin "1") (pinfunction "1_1") (pintype "passive"))
      (node (ref "R40") (pin "2") (pinfunction "2_2") (pintype "passive"))
      (node (ref "U$15") (pin "2") (pinfunction "FB_2") (pintype "bidirectional"))
    )
    (net (code "43") (name "Net-(U$15-NR{slash}SS)") (class "Default")
      (node (ref "C45") (pin "1") (pinfunction "1_1") (pintype "passive"))
      (node (ref "U$15") (pin "6") (pinfunction "NR/SS_6") (pintype "bidirectional"))
    )
    (net (code "44") (name "Net-(U1-USBDM)") (class "Default")
      (node (ref "R14") (pin "2") (pinfunction "2_2") (pintype "passive"))
      (node (ref "U1") (pin "12") (pinfunction "USBDM_12") (pintype "bidirectional"))
    )
    (net (code "45") (name "Net-(U1-USBDP)") (class "Default")
      (node (ref "R15") (pin "2") (pinfunction "2_2") (pintype "passive"))
      (node (ref "U1") (pin "11") (pinfunction "USBDP_11") (pintype "bidirectional"))
    )
    (net (code "46") (name "Net-(U3-PROG)") (class "Default")
      (node (ref "R17") (pin "2") (pinfunction "2_2") (pintype "passive"))
      (node (ref "U3") (pin "5") (pinfunction "PROG_5") (pintype "input"))
    )
    (net (code "47") (name "Net-(U3-STAT)") (class "Default")
      (node (ref "CHG2") (pin "C") (pinfunction "C_C") (pintype "passive"))
      (node (ref "U3") (pin "1") (pinfunction "STAT_1") (pintype "output"))
    )
    (net (code "48") (name "REFN0") (class "Default")
      (node (ref "TP65") (pin "TP") (pinfunction "TP_TP") (pintype "input"))
      (node (ref "U$9") (pin "8") (pinfunction "REFN0_8") (pintype "bidirectional"))
    )
    (net (code "49") (name "REFP0") (class "Default")
      (node (ref "TP58") (pin "TP") (pinfunction "TP_TP") (pintype "input"))
      (node (ref "U$9") (pin "9") (pinfunction "REFP0_9") (pintype "bidirectional"))
    )
    (net (code "50") (name "RTS") (class "Default")
      (node (ref "Q1") (pin "4") (pinfunction "E_4") (pintype "passive"))
      (node (ref "R10") (pin "1") (pinfunction "1_1") (pintype "passive"))
      (node (ref "U1") (pin "2") (pinfunction "~{RTS}_2") (pintype "bidirectional"))
    )
    (net (code "51") (name "RXD") (class "Default")
      (node (ref "R13") (pin "2") (pinfunction "2_2") (pintype "passive"))
      (node (ref "U1") (pin "4") (pinfunction "RXD_4") (pintype "bidirectional"))
    )
    (net (code "52") (name "SCL") (class "Default")
      (node (ref "IC1") (pin "42") (pinfunction "IO21_42") (pintype "power_in"))
      (node (ref "J4") (pin "4") (pinfunction "4_4") (pintype "passive"))
      (node (ref "R3") (pin "1") (pinfunction "1_1") (pintype "passive"))
    )
    (net (code "53") (name "SCL1") (class "Default")
      (node (ref "IC1") (pin "14") (pinfunction "IO25_14") (pintype "bidirectional"))
      (node (ref "J1") (pin "4") (pinfunction "4_4") (pintype "passive"))
      (node (ref "R18") (pin "1") (pinfunction "1_1") (pintype "passive"))
    )
    (net (code "54") (name "SCLK") (class "Default")
      (node (ref "IC1") (pin "35") (pinfunction "IO18_35") (pintype "bidirectional"))
      (node (ref "U$9") (pin "1") (pinfunction "SCLK_1") (pintype "bidirectional"))
    )
    (net (code "55") (name "SDA") (class "Default")
      (node (ref "IC1") (pin "16") (pinfunction "IO27_16") (pintype "bidirectional"))
      (node (ref "J4") (pin "3") (pinfunction "3_3") (pintype "passive"))
      (node (ref "R4") (pin "1") (pinfunction "1_1") (pintype "passive"))
    )
    (net (code "56") (name "SDA1") (class "Default")
      (node (ref "IC1") (pin "15") (pinfunction "IO26_15") (pintype "bidirectional"))
      (node (ref "J1") (pin "3") (pinfunction "3_3") (pintype "passive"))
      (node (ref "R5") (pin "1") (pinfunction "1_1") (pintype "passive"))
    )
    (net (code "57") (name "SENSOR_CAPN") (class "Default")
      (node (ref "IC1") (pin "7") (pinfunction "SENSOR_CAPN_7") (pintype "power_in"))
    )
    (net (code "58") (name "TXD") (class "Default")
      (node (ref "R12") (pin "2") (pinfunction "2_2") (pintype "passive"))
      (node (ref "U1") (pin "20") (pinfunction "TXD_20") (pintype "bidirectional"))
    )
    (net (code "59") (name "U0RXD") (class "Default")
      (node (ref "IC1") (pin "40") (pinfunction "U0RXD_40") (pintype "bidirectional"))
      (node (ref "R12") (pin "1") (pinfunction "1_1") (pintype "passive"))
    )
    (net (code "60") (name "U0TXD") (class "Default")
      (node (ref "IC1") (pin "41") (pinfunction "U0TXD_41") (pintype "bidirectional"))
      (node (ref "R13") (pin "1") (pinfunction "1_1") (pintype "passive"))
    )
    (net (code "61") (name "VBAT") (class "Default")
      (node (ref "C65") (pin "1") (pinfunction "1_1") (pintype "passive"))
      (node (ref "JP6") (pin "2") (pinfunction "2_2") (pintype "passive"))
      (node (ref "Q2") (pin "3") (pinfunction "D_3") (pintype "passive"))
      (node (ref "R25") (pin "2") (pinfunction "2_2") (pintype "passive"))
      (node (ref "U3") (pin "3") (pinfunction "VBAT_3") (pintype "power_in"))
    )
    (net (code "62") (name "VCC") (class "Default")
      (node (ref "C44") (pin "1") (pinfunction "1_1") (pintype "passive"))
      (node (ref "C83") (pin "1") (pinfunction "1_1") (pintype "passive"))
      (node (ref "R20") (pin "1") (pinfunction "1_1") (pintype "passive"))
      (node (ref "TP41") (pin "TP") (pinfunction "TP_TP") (pintype "input"))
      (node (ref "U$13") (pin "4") (pinfunction "VOUT_4") (pintype "bidirectional"))
      (node (ref "U$15") (pin "5") (pinfunction "EN_5") (pintype "bidirectional"))
      (node (ref "U$15") (pin "8") (pinfunction "IN_8") (pintype "bidirectional"))
    )
    (net (code "63") (name "VIN") (class "Default")
      (node (ref "C1") (pin "1") (pinfunction "1_1") (pintype "passive"))
      (node (ref "C63") (pin "1") (pinfunction "1_1") (pintype "passive"))
      (node (ref "C72") (pin "2") (pinfunction "2_2") (pintype "passive"))
      (node (ref "D1") (pin "C") (pinfunction "C_C") (pintype "passive"))
      (node (ref "Q2") (pin "2") (pinfunction "S_2") (pintype "passive"))
      (node (ref "S2") (pin "3") (pinfunction "S_3") (pintype "passive"))
      (node (ref "U$1") (pin "P$1") (pinfunction "1_P$1") (pintype "passive"))
      (node (ref "U$13") (pin "1") (pinfunction "VIN_1") (pintype "bidirectional"))
      (node (ref "U8") (pin "1") (pinfunction "IN_1") (pintype "input"))
    )
    (net (code "64") (name "VUSB") (class "Default")
      (node (ref "C60") (pin "1") (pinfunction "1_1") (pintype "passive"))
      (node (ref "C61") (pin "1") (pinfunction "1_1") (pintype "passive"))
      (node (ref "C64") (pin "1") (pinfunction "1_1") (pintype "passive"))
      (node (ref "D1") (pin "A") (pinfunction "A_A") (pintype "passive"))
      (node (ref "JP7") (pin "1") (pinfunction "VCC_1") (pintype "bidirectional"))
      (node (ref "Q2") (pin "1") (pinfunction "G_1") (pintype "passive"))
      (node (ref "R16") (pin "1") (pinfunction "1_1") (pintype "passive"))
      (node (ref "R23") (pin "2") (pinfunction "2_2") (pintype "passive"))
      (node (ref "U1") (pin "15") (pinfunction "VCC_15") (pintype "bidirectional"))
      (node (ref "U3") (pin "4") (pinfunction "VIN_4") (pintype "power_in"))
    )
    (net (code "65") (name "WS2812") (class "Default")
      (node (ref "IC1") (pin "17") (pinfunction "IO14_17") (pintype "bidirectional"))
      (node (ref "R6") (pin "2") (pinfunction "2_2") (pintype "passive"))
    )
    (net (code "66") (name "unconnected-(IC1A-CAP1_NC-Pad48)") (class "Default")
      (node (ref "IC1") (pin "48") (pinfunction "CAP1_NC_48") (pintype "bidirectional"))
    )
    (net (code "67") (name "unconnected-(IC1A-CAP2_NC-Pad47)") (class "Default")
      (node (ref "IC1") (pin "47") (pinfunction "CAP2_NC_47") (pintype "bidirectional"))
    )
    (net (code "68") (name "unconnected-(IC1A-IO2-Pad22)") (class "Default")
      (node (ref "IC1") (pin "22") (pinfunction "IO2_22") (pintype "bidirectional"))
    )
    (net (code "69") (name "unconnected-(IC1A-IO5-Pad34)") (class "Default")
      (node (ref "IC1") (pin "34") (pinfunction "IO5_34") (pintype "bidirectional"))
    )
    (net (code "70") (name "unconnected-(IC1A-IO13-Pad20)") (class "Default")
      (node (ref "IC1") (pin "20") (pinfunction "IO13_20") (pintype "bidirectional"))
    )
    (net (code "71") (name "unconnected-(IC1A-SD0-Pad32)") (class "Default")
      (node (ref "IC1") (pin "32") (pinfunction "SD0_32") (pintype "bidirectional"))
    )
    (net (code "72") (name "unconnected-(IC1A-SD1-Pad33)") (class "Default")
      (node (ref "IC1") (pin "33") (pinfunction "SD1_33") (pintype "bidirectional"))
    )
    (net (code "73") (name "unconnected-(IC1A-SENSOR_CAPP-Pad6)") (class "Default")
      (node (ref "IC1") (pin "6") (pinfunction "SENSOR_CAPP_6") (pintype "bidirectional"))
    )
    (net (code "74") (name "unconnected-(IC1A-XTAL_N_NC-Pad44)") (class "Default")
      (node (ref "IC1") (pin "44") (pinfunction "XTAL_N_NC_44") (pintype "bidirectional"))
    )
    (net (code "75") (name "unconnected-(IC1A-XTAL_P_NC-Pad45)") (class "Default")
      (node (ref "IC1") (pin "45") (pinfunction "XTAL_P_NC_45") (pintype "bidirectional"))
    )
    (net (code "76") (name "unconnected-(JP7-ID-Pad4)") (class "Default")
      (node (ref "JP7") (pin "4") (pinfunction "ID_4") (pintype "bidirectional"))
    )
    (net (code "77") (name "unconnected-(LED1-DO-Pad2-DOUT)") (class "Default")
      (node (ref "LED1") (pin "2-DOUT") (pinfunction "DO_2-DOUT") (pintype "output"))
    )
    (net (code "78") (name "unconnected-(SW2-P1-PadA')") (class "Default")
      (node (ref "SW2") (pin "A'") (pinfunction "P1_A'") (pintype "passive"))
    )
    (net (code "79") (name "unconnected-(U1-CBUS0-Pad18)") (class "Default")
      (node (ref "U1") (pin "18") (pinfunction "CBUS0_18") (pintype "bidirectional"))
    )
    (net (code "80") (name "unconnected-(U1-CBUS1-Pad17)") (class "Default")
      (node (ref "U1") (pin "17") (pinfunction "CBUS1_17") (pintype "bidirectional"))
    )
    (net (code "81") (name "unconnected-(U1-CBUS2-Pad10)") (class "Default")
      (node (ref "U1") (pin "10") (pinfunction "CBUS2_10") (pintype "bidirectional"))
    )
    (net (code "82") (name "unconnected-(U1-CBUS3-Pad19)") (class "Default")
      (node (ref "U1") (pin "19") (pinfunction "CBUS3_19") (pintype "bidirectional"))
    )
    (net (code "83") (name "unconnected-(U1-~{CTS}-Pad9)") (class "Default")
      (node (ref "U1") (pin "9") (pinfunction "~{CTS}_9") (pintype "bidirectional"))
    )
    (net (code "84") (name "unconnected-(U1-~{DCD}-Pad8)") (class "Default")
      (node (ref "U1") (pin "8") (pinfunction "~{DCD}_8") (pintype "bidirectional"))
    )
    (net (code "85") (name "unconnected-(U1-~{DSR}-Pad7)") (class "Default")
      (node (ref "U1") (pin "7") (pinfunction "~{DSR}_7") (pintype "bidirectional"))
    )
    (net (code "86") (name "unconnected-(U1-~{RI}-Pad5)") (class "Default")
      (node (ref "U1") (pin "5") (pinfunction "~{RI}_5") (pintype "bidirectional"))
    )
    (net (code "87") (name "unconnected-(U8-BP-Pad4)") (class "Default")
      (node (ref "U8") (pin "4") (pinfunction "BP_4") (pintype "input"))
    )
    (net (code "88") (name "~{CS1}") (class "Default")
      (node (ref "IC1") (pin "38") (pinfunction "IO19_38") (pintype "bidirectional"))
      (node (ref "U$9") (pin "2") (pinfunction "~{CS}_2") (pintype "bidirectional"))
    )
    (net (code "89") (name "~{DRDY}") (class "Default")
      (node (ref "IC1") (pin "10") (pinfunction "IO34_10") (pintype "bidirectional"))
      (node (ref "U$9") (pin "14") (pinfunction "~{DRDY}_14") (pintype "bidirectional"))
    )
  )
)
